# OLED.net
KiCad netlist of a schematic drawn in Altium Designer
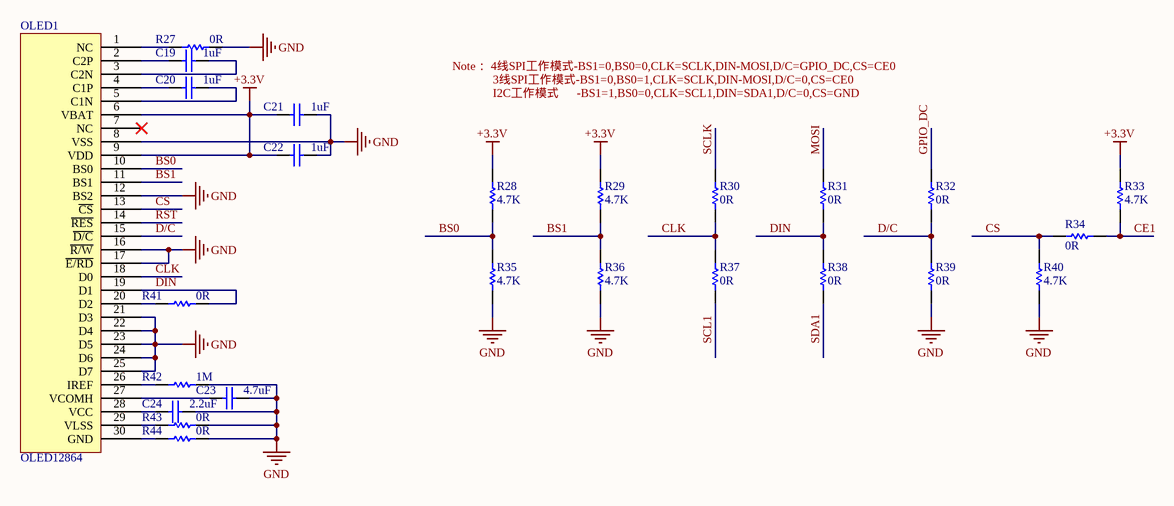
[diagram p0: OLED.SchDoc]

(export (version "E")
  (design (tool "Eeschema 10.0.6"))
  (components
    (comp (ref "C19")
      (value "1uF")
      (footprint "C0603")
      (description "Capacitor (Semiconductor SIM Model)")
      (fields (field (name "PUBLISHER") "Altium Limited"))
      (libsource (lib "Miscellaneous Devices") (part "Cap Semi"))
    )
    (comp (ref "C20")
      (value "1uF")
      (footprint "C0603")
      (description "Capacitor (Semiconductor SIM Model)")
      (fields (field (name "PUBLISHER") "Altium Limited"))
      (libsource (lib "Miscellaneous Devices") (part "Cap Semi"))
    )
    (comp (ref "C21")
      (value "1uF")
      (footprint "C0603")
      (description "Capacitor (Semiconductor SIM Model)")
      (fields (field (name "PUBLISHER") "Altium Limited"))
      (libsource (lib "Miscellaneous Devices") (part "Cap Semi"))
    )
    (comp (ref "C22")
      (value "1uF")
      (footprint "C0603")
      (description "Capacitor (Semiconductor SIM Model)")
      (fields (field (name "PUBLISHER") "Altium Limited"))
      (libsource (lib "Miscellaneous Devices") (part "Cap Semi"))
    )
    (comp (ref "C23")
      (value "4.7uF")
      (footprint "C0603")
      (description "Capacitor (Semiconductor SIM Model)")
      (fields (field (name "PUBLISHER") "Altium Limited"))
      (libsource (lib "Miscellaneous Devices") (part "Cap Semi"))
    )
    (comp (ref "C24")
      (value "2.2uF")
      (footprint "C0603")
      (description "Capacitor (Semiconductor SIM Model)")
      (fields (field (name "PUBLISHER") "Altium Limited"))
      (libsource (lib "Miscellaneous Devices") (part "Cap Semi"))
    )
    (comp (ref "OLED1")
      (value "OLED12864")
      (footprint "OLED_128*64_0.96_30PIN")
      (description "OLED 12864 0.9inch")
      (libsource (lib "RaspberryPi_Hat_schlib") (part "OLED12864"))
    )
    (comp (ref "R27")
      (value "0R")
      (footprint "R0603")
      (description "Resistor")
      (fields (field (name "PUBLISHER") "Altium Limited"))
      (libsource (lib "Miscellaneous Devices") (part "Res1"))
    )
    (comp (ref "R28")
      (value "4.7K")
      (footprint "R0603")
      (description "Resistor")
      (fields (field (name "PUBLISHER") "Altium Limited"))
      (libsource (lib "Miscellaneous Devices") (part "Res1"))
    )
    (comp (ref "R29")
      (value "4.7K")
      (footprint "R0603")
      (description "Resistor")
      (fields (field (name "PUBLISHER") "Altium Limited"))
      (libsource (lib "Miscellaneous Devices") (part "Res1"))
    )
    (comp (ref "R30")
      (value "0R")
      (footprint "R0603")
      (description "Resistor")
      (fields (field (name "PUBLISHER") "Altium Limited"))
      (libsource (lib "Miscellaneous Devices") (part "Res1"))
    )
    (comp (ref "R31")
      (value "0R")
      (footprint "R0603")
      (description "Resistor")
      (fields (field (name "PUBLISHER") "Altium Limited"))
      (libsource (lib "Miscellaneous Devices") (part "Res1"))
    )
    (comp (ref "R32")
      (value "0R")
      (footprint "R0603")
      (description "Resistor")
      (fields (field (name "PUBLISHER") "Altium Limited"))
      (libsource (lib "Miscellaneous Devices") (part "Res1"))
    )
    (comp (ref "R33")
      (value "4.7K")
      (footprint "R0603")
      (description "Resistor")
      (fields (field (name "PUBLISHER") "Altium Limited"))
      (libsource (lib "Miscellaneous Devices") (part "Res1"))
    )
    (comp (ref "R34")
      (value "0R")
      (footprint "R0603")
      (description "Resistor")
      (fields (field (name "PUBLISHER") "Altium Limited"))
      (libsource (lib "Miscellaneous Devices") (part "Res1"))
    )
    (comp (ref "R35")
      (value "4.7K")
      (footprint "R0603")
      (description "Resistor")
      (fields (field (name "PUBLISHER") "Altium Limited"))
      (libsource (lib "Miscellaneous Devices") (part "Res1"))
    )
    (comp (ref "R36")
      (value "4.7K")
      (footprint "R0603")
      (description "Resistor")
      (fields (field (name "PUBLISHER") "Altium Limited"))
      (libsource (lib "Miscellaneous Devices") (part "Res1"))
    )
    (comp (ref "R37")
      (value "0R")
      (footprint "R0603")
      (description "Resistor")
      (fields (field (name "PUBLISHER") "Altium Limited"))
      (libsource (lib "Miscellaneous Devices") (part "Res1"))
    )
    (comp (ref "R38")
      (value "0R")
      (footprint "R0603")
      (description "Resistor")
      (fields (field (name "PUBLISHER") "Altium Limited"))
      (libsource (lib "Miscellaneous Devices") (part "Res1"))
    )
    (comp (ref "R39")
      (value "0R")
      (footprint "R0603")
      (description "Resistor")
      (fields (field (name "PUBLISHER") "Altium Limited"))
      (libsource (lib "Miscellaneous Devices") (part "Res1"))
    )
    (comp (ref "R40")
      (value "4.7K")
      (footprint "R0603")
      (description "Resistor")
      (fields (field (name "PUBLISHER") "Altium Limited"))
      (libsource (lib "Miscellaneous Devices") (part "Res1"))
    )
    (comp (ref "R41")
      (value "0R")
      (footprint "R0603")
      (description "Resistor")
      (fields (field (name "PUBLISHER") "Altium Limited"))
      (libsource (lib "Miscellaneous Devices") (part "Res1"))
    )
    (comp (ref "R42")
      (value "1M")
      (footprint "R0603")
      (description "Resistor")
      (fields (field (name "PUBLISHER") "Altium Limited"))
      (libsource (lib "Miscellaneous Devices") (part "Res1"))
    )
    (comp (ref "R43")
      (value "0R")
      (footprint "R0603")
      (description "Resistor")
      (fields (field (name "PUBLISHER") "Altium Limited"))
      (libsource (lib "Miscellaneous Devices") (part "Res1"))
    )
    (comp (ref "R44")
      (value "0R")
      (footprint "R0603")
      (description "Resistor")
      (fields (field (name "PUBLISHER") "Altium Limited"))
      (libsource (lib "Miscellaneous Devices") (part "Res1"))
    )
  )
  (nets
    (net (code "1") (name "+3.3V") (class "Default")
      (node (ref "C21") (pin "2") (pinfunction "2_2") (pintype "passive"))
      (node (ref "C22") (pin "2") (pinfunction "2_2") (pintype "passive"))
      (node (ref "OLED1") (pin "6") (pinfunction "VBAT_6") (pintype "passive"))
      (node (ref "OLED1") (pin "9") (pinfunction "VDD_9") (pintype "passive"))
      (node (ref "R28") (pin "1") (pinfunction "1_1") (pintype "passive"))
      (node (ref "R29") (pin "1") (pinfunction "1_1") (pintype "passive"))
      (node (ref "R33") (pin "1") (pinfunction "1_1") (pintype "passive"))
    )
    (net (code "2") (name "/BS0") (class "Default")
      (node (ref "OLED1") (pin "10") (pinfunction "BS0_10") (pintype "passive"))
      (node (ref "R28") (pin "2") (pinfunction "2_2") (pintype "passive"))
      (node (ref "R35") (pin "1") (pinfunction "1_1") (pintype "passive"))
    )
    (net (code "3") (name "/BS1") (class "Default")
      (node (ref "OLED1") (pin "11") (pinfunction "BS1_11") (pintype "passive"))
      (node (ref "R29") (pin "2") (pinfunction "2_2") (pintype "passive"))
      (node (ref "R36") (pin "1") (pinfunction "1_1") (pintype "passive"))
    )
    (net (code "4") (name "/CE1") (class "Default")
      (node (ref "R33") (pin "2") (pinfunction "2_2") (pintype "passive"))
      (node (ref "R34") (pin "2") (pinfunction "2_2") (pintype "passive"))
    )
    (net (code "5") (name "/CLK") (class "Default")
      (node (ref "OLED1") (pin "18") (pinfunction "D0_18") (pintype "passive"))
      (node (ref "R30") (pin "2") (pinfunction "2_2") (pintype "passive"))
      (node (ref "R37") (pin "1") (pinfunction "1_1") (pintype "passive"))
    )
    (net (code "6") (name "/CS") (class "Default")
      (node (ref "OLED1") (pin "13") (pinfunction "~{CS}_13") (pintype "passive"))
      (node (ref "R34") (pin "1") (pinfunction "1_1") (pintype "passive"))
      (node (ref "R40") (pin "1") (pinfunction "1_1") (pintype "passive"))
    )
    (net (code "7") (name "/DIN") (class "Default")
      (node (ref "OLED1") (pin "19") (pinfunction "D1_19") (pintype "passive"))
      (node (ref "R31") (pin "2") (pinfunction "2_2") (pintype "passive"))
      (node (ref "R38") (pin "1") (pinfunction "1_1") (pintype "passive"))
      (node (ref "R41") (pin "1") (pinfunction "1_1") (pintype "passive"))
    )
    (net (code "8") (name "/D{slash}C") (class "Default")
      (node (ref "OLED1") (pin "15") (pinfunction "~{D/C}_15") (pintype "passive"))
      (node (ref "R32") (pin "2") (pinfunction "2_2") (pintype "passive"))
      (node (ref "R39") (pin "1") (pinfunction "1_1") (pintype "passive"))
    )
    (net (code "9") (name "/GPIO_DC") (class "Default")
      (node (ref "R32") (pin "1") (pinfunction "1_1") (pintype "passive"))
    )
    (net (code "10") (name "/MOSI") (class "Default")
      (node (ref "R31") (pin "1") (pinfunction "1_1") (pintype "passive"))
    )
    (net (code "11") (name "/RST") (class "Default")
      (node (ref "OLED1") (pin "14") (pinfunction "~{RES}_14") (pintype "passive"))
    )
    (net (code "12") (name "/SCL1") (class "Default")
      (node (ref "R37") (pin "2") (pinfunction "2_2") (pintype "passive"))
    )
    (net (code "13") (name "/SCLK") (class "Default")
      (node (ref "R30") (pin "1") (pinfunction "1_1") (pintype "passive"))
    )
    (net (code "14") (name "/SDA1") (class "Default")
      (node (ref "R38") (pin "2") (pinfunction "2_2") (pintype "passive"))
    )
    (net (code "15") (name "GND") (class "Default")
      (node (ref "C21") (pin "1") (pinfunction "1_1") (pintype "passive"))
      (node (ref "C22") (pin "1") (pinfunction "1_1") (pintype "passive"))
      (node (ref "C23") (pin "1") (pinfunction "1_1") (pintype "passive"))
      (node (ref "C24") (pin "1") (pinfunction "1_1") (pintype "passive"))
      (node (ref "OLED1") (pin "12") (pinfunction "BS2_12") (pintype "passive"))
      (node (ref "OLED1") (pin "16") (pinfunction "~{R/W}_16") (pintype "passive"))
      (node (ref "OLED1") (pin "17") (pinfunction "~{E/RD}_17") (pintype "passive"))
      (node (ref "OLED1") (pin "21") (pinfunction "D3_21") (pintype "passive"))
      (node (ref "OLED1") (pin "22") (pinfunction "D4_22") (pintype "passive"))
      (node (ref "OLED1") (pin "23") (pinfunction "D5_23") (pintype "passive"))
      (node (ref "OLED1") (pin "24") (pinfunction "D6_24") (pintype "passive"))
      (node (ref "OLED1") (pin "25") (pinfunction "D7_25") (pintype "passive"))
      (node (ref "OLED1") (pin "8") (pinfunction "VSS_8") (pintype "passive"))
      (node (ref "R27") (pin "1") (pinfunction "1_1") (pintype "passive"))
      (node (ref "R35") (pin "2") (pinfunction "2_2") (pintype "passive"))
      (node (ref "R36") (pin "2") (pinfunction "2_2") (pintype "passive"))
      (node (ref "R39") (pin "2") (pinfunction "2_2") (pintype "passive"))
      (node (ref "R40") (pin "2") (pinfunction "2_2") (pintype "passive"))
      (node (ref "R42") (pin "1") (pinfunction "1_1") (pintype "passive"))
      (node (ref "R43") (pin "1") (pinfunction "1_1") (pintype "passive"))
      (node (ref "R44") (pin "1") (pinfunction "1_1") (pintype "passive"))
    )
    (net (code "16") (name "Net-(OLED1-C1N)") (class "Default")
      (node (ref "C20") (pin "1") (pinfunction "1_1") (pintype "passive"))
      (node (ref "OLED1") (pin "5") (pinfunction "C1N_5") (pintype "passive"))
    )
    (net (code "17") (name "Net-(OLED1-C1P)") (class "Default")
      (node (ref "C20") (pin "2") (pinfunction "2_2") (pintype "passive"))
      (node (ref "OLED1") (pin "4") (pinfunction "C1P_4") (pintype "passive"))
    )
    (net (code "18") (name "Net-(OLED1-C2N)") (class "Default")
      (node (ref "C19") (pin "1") (pinfunction "1_1") (pintype "passive"))
      (node (ref "OLED1") (pin "3") (pinfunction "C2N_3") (pintype "passive"))
    )
    (net (code "19") (name "Net-(OLED1-C2P)") (class "Default")
      (node (ref "C19") (pin "2") (pinfunction "2_2") (pintype "passive"))
      (node (ref "OLED1") (pin "2") (pinfunction "C2P_2") (pintype "passive"))
    )
    (net (code "20") (name "Net-(OLED1-D2)") (class "Default")
      (node (ref "OLED1") (pin "20") (pinfunction "D2_20") (pintype "passive"))
      (node (ref "R41") (pin "2") (pinfunction "2_2") (pintype "passive"))
    )
    (net (code "21") (name "Net-(OLED1-GND)") (class "Default")
      (node (ref "OLED1") (pin "30") (pinfunction "GND_30") (pintype "passive"))
      (node (ref "R44") (pin "2") (pinfunction "2_2") (pintype "passive"))
    )
    (net (code "22") (name "Net-(OLED1-IREF)") (class "Default")
      (node (ref "OLED1") (pin "26") (pinfunction "IREF_26") (pintype "passive"))
      (node (ref "R42") (pin "2") (pinfunction "2_2") (pintype "passive"))
    )
    (net (code "23") (name "Net-(OLED1-NC-Pad1)") (class "Default")
      (node (ref "OLED1") (pin "1") (pinfunction "NC_1") (pintype "passive"))
      (node (ref "R27") (pin "2") (pinfunction "2_2") (pintype "passive"))
    )
    (net (code "24") (name "Net-(OLED1-VCC)") (class "Default")
      (node (ref "C24") (pin "2") (pinfunction "2_2") (pintype "passive"))
      (node (ref "OLED1") (pin "28") (pinfunction "VCC_28") (pintype "passive"))
    )
    (net (code "25") (name "Net-(OLED1-VCOMH)") (class "Default")
      (node (ref "C23") (pin "2") (pinfunction "2_2") (pintype "passive"))
      (node (ref "OLED1") (pin "27") (pinfunction "VCOMH_27") (pintype "passive"))
    )
    (net (code "26") (name "Net-(OLED1-VLSS)") (class "Default")
      (node (ref "OLED1") (pin "29") (pinfunction "VLSS_29") (pintype "passive"))
      (node (ref "R43") (pin "2") (pinfunction "2_2") (pintype "passive"))
    )
    (net (code "27") (name "unconnected-(OLED1-NC-Pad7)") (class "Default")
      (node (ref "OLED1") (pin "7") (pinfunction "NC_7") (pintype "passive+no_connect"))
    )
  )
)
